# klokun.net
KiCad netlist of a schematic drawn in Altium Designer
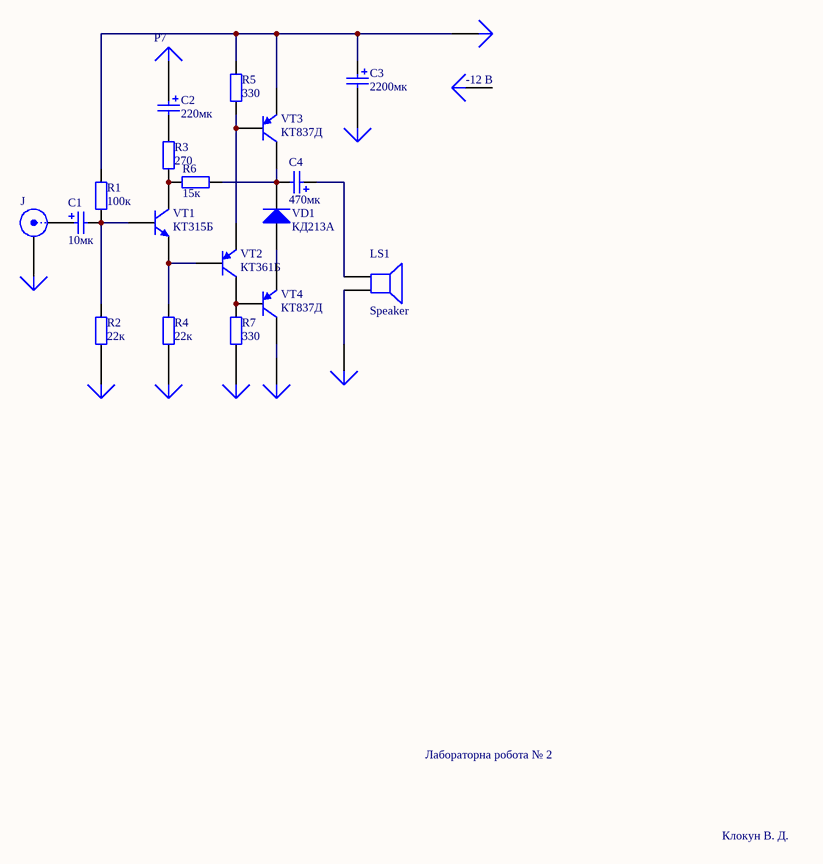
[diagram p0: klokun.SchDoc]

(export (version "E")
  (design (tool "Eeschema 10.0.6"))
  (components
    (comp (ref "C1")
      (value "10мк")
      (footprint "CAPPA14.05-10.5x6.3")
      (description "Polarized Capacitor (Axial)")
      (fields (field (name "Comment") "Cap Pol2") (field (name "PUBLISHER") "Altium Limited"))
      (libsource (lib "Miscellaneous Devices") (part "Cap Pol2"))
    )
    (comp (ref "C2")
      (value "220мк")
      (footprint "CAPPA14.05-10.5x6.3")
      (description "Polarized Capacitor (Axial)")
      (fields (field (name "Comment") "Cap Pol2") (field (name "PUBLISHER") "Altium Limited"))
      (libsource (lib "Miscellaneous Devices") (part "Cap Pol2"))
    )
    (comp (ref "C3")
      (value "2200мк")
      (footprint "CAPPA14.05-10.5x6.3")
      (description "Polarized Capacitor (Axial)")
      (fields (field (name "Comment") "Cap Pol2") (field (name "PUBLISHER") "Altium Limited"))
      (libsource (lib "Miscellaneous Devices") (part "Cap Pol2"))
    )
    (comp (ref "C4")
      (value "470мк")
      (footprint "CAPPA14.05-10.5x6.3")
      (description "Polarized Capacitor (Axial)")
      (fields (field (name "Comment") "Cap Pol2") (field (name "PUBLISHER") "Altium Limited"))
      (libsource (lib "Miscellaneous Devices") (part "Cap Pol2"))
    )
    (comp (ref "J")
      (value "BNC")
      (footprint "BNC_RA CON")
      (description "BNC Elbow Connector")
      (fields (field (name "PUBLISHER") "Altium Limited"))
      (libsource (lib "Miscellaneous Connectors") (part "BNC"))
    )
    (comp (ref "LS1")
      (value "Speaker")
      (footprint "PIN2")
      (description "Loudspeaker")
      (fields (field (name "PUBLISHER") "Altium Limited"))
      (libsource (lib "Miscellaneous Devices") (part "Speaker"))
    )
    (comp (ref "P1")
      (value "Plug")
      (footprint "PIN1")
      (fields (field (name "PUBLISHER") "Altium Limited"))
      (libsource (lib "Miscellaneous Connectors") (part "Plug"))
    )
    (comp (ref "P2")
      (value "Plug")
      (footprint "PIN1")
      (fields (field (name "PUBLISHER") "Altium Limited"))
      (libsource (lib "Miscellaneous Connectors") (part "Plug"))
    )
    (comp (ref "P3")
      (value "Plug")
      (footprint "PIN1")
      (fields (field (name "PUBLISHER") "Altium Limited"))
      (libsource (lib "Miscellaneous Connectors") (part "Plug"))
    )
    (comp (ref "P4")
      (value "Plug")
      (footprint "PIN1")
      (fields (field (name "PUBLISHER") "Altium Limited"))
      (libsource (lib "Miscellaneous Connectors") (part "Plug"))
    )
    (comp (ref "P5")
      (value "Plug")
      (footprint "PIN1")
      (fields (field (name "PUBLISHER") "Altium Limited"))
      (libsource (lib "Miscellaneous Connectors") (part "Plug"))
    )
    (comp (ref "P6")
      (value "Plug")
      (footprint "PIN1")
      (fields (field (name "PUBLISHER") "Altium Limited"))
      (libsource (lib "Miscellaneous Connectors") (part "Plug"))
    )
    (comp (ref "P7")
      (value "Plug")
      (footprint "PIN1")
      (fields (field (name "PUBLISHER") "Altium Limited"))
      (libsource (lib "Miscellaneous Connectors") (part "Plug"))
    )
    (comp (ref "P8")
      (value "Plug")
      (footprint "PIN1")
      (fields (field (name "PUBLISHER") "Altium Limited"))
      (libsource (lib "Miscellaneous Connectors") (part "Plug"))
    )
    (comp (ref "P9")
      (value "Plug")
      (footprint "PIN1")
      (fields (field (name "PUBLISHER") "Altium Limited"))
      (libsource (lib "Miscellaneous Connectors") (part "Plug"))
    )
    (comp (ref "P10")
      (value "-12 В")
      (footprint "PIN1")
      (description "Plug")
      (fields (field (name "PUBLISHER") "Altium Limited"))
      (libsource (lib "Miscellaneous Connectors") (part "Plug"))
    )
    (comp (ref "R1")
      (value "100к")
      (footprint "AXIAL-0.4")
      (description "Resistor")
      (fields (field (name "Comment") "Res2") (field (name "PUBLISHER") "Altium Limited"))
      (libsource (lib "Miscellaneous Devices") (part "Res2"))
    )
    (comp (ref "R2")
      (value "22к")
      (footprint "AXIAL-0.4")
      (description "Resistor")
      (fields (field (name "Comment") "Res2") (field (name "PUBLISHER") "Altium Limited"))
      (libsource (lib "Miscellaneous Devices") (part "Res2"))
    )
    (comp (ref "R3")
      (value "270")
      (footprint "AXIAL-0.4")
      (description "Resistor")
      (fields (field (name "Comment") "Res2") (field (name "PUBLISHER") "Altium Limited"))
      (libsource (lib "Miscellaneous Devices") (part "Res2"))
    )
    (comp (ref "R4")
      (value "22к")
      (footprint "AXIAL-0.4")
      (description "Resistor")
      (fields (field (name "Comment") "Res2") (field (name "PUBLISHER") "Altium Limited"))
      (libsource (lib "Miscellaneous Devices") (part "Res2"))
    )
    (comp (ref "R5")
      (value "330")
      (footprint "AXIAL-0.4")
      (description "Resistor")
      (fields (field (name "Comment") "Res2") (field (name "PUBLISHER") "Altium Limited"))
      (libsource (lib "Miscellaneous Devices") (part "Res2"))
    )
    (comp (ref "R6")
      (value "15к")
      (footprint "AXIAL-0.4")
      (description "Resistor")
      (fields (field (name "Comment") "Res2") (field (name "PUBLISHER") "Altium Limited"))
      (libsource (lib "") (part "Res2_1"))
    )
    (comp (ref "R7")
      (value "330")
      (footprint "AXIAL-0.4")
      (description "Resistor")
      (fields (field (name "Comment") "Res2") (field (name "PUBLISHER") "Altium Limited"))
      (libsource (lib "Miscellaneous Devices") (part "Res2"))
    )
    (comp (ref "VD1")
      (value "КД213А")
      (footprint "SMC")
      (description "Default Diode")
      (fields (field (name "PUBLISHER") "Altium Limited"))
      (libsource (lib "Miscellaneous Devices") (part "Diode"))
    )
    (comp (ref "VT1")
      (value "КТ315Б")
      (footprint "TO-226")
      (description "NPN Bipolar Transistor")
      (fields (field (name "PUBLISHER") "Altium Limited"))
      (libsource (lib "Miscellaneous Devices") (part "NPN"))
    )
    (comp (ref "VT2")
      (value "КТ361Б")
      (footprint "SOT-23B")
      (description "PNP Bipolar Transistor")
      (fields (field (name "PUBLISHER") "Altium Limited"))
      (libsource (lib "Miscellaneous Devices") (part "PNP"))
    )
    (comp (ref "VT3")
      (value "КТ837Д")
      (footprint "SOT-23B")
      (description "PNP Bipolar Transistor")
      (fields (field (name "PUBLISHER") "Altium Limited"))
      (libsource (lib "Miscellaneous Devices") (part "PNP"))
    )
    (comp (ref "VT4")
      (value "КТ837Д")
      (footprint "SOT-23B")
      (description "PNP Bipolar Transistor")
      (fields (field (name "PUBLISHER") "Altium Limited"))
      (libsource (lib "Miscellaneous Devices") (part "PNP"))
    )
  )
  (nets
    (net (code "1") (name "Net-(C2-Pad1)") (class "Default")
      (node (ref "C2") (pin "1") (pinfunction "1_1") (pintype "passive"))
      (node (ref "P7") (pin "1") (pinfunction "1_1") (pintype "passive"))
    )
    (net (code "2") (name "Net-(C2-Pad2)") (class "Default")
      (node (ref "C2") (pin "2") (pinfunction "2_2") (pintype "passive"))
      (node (ref "R3") (pin "2") (pinfunction "2_2") (pintype "passive"))
    )
    (net (code "3") (name "Net-(C3-Pad2)") (class "Default")
      (node (ref "C3") (pin "2") (pinfunction "2_2") (pintype "passive"))
      (node (ref "P1") (pin "1") (pinfunction "1_1") (pintype "passive"))
    )
    (net (code "4") (name "Net-(C4-Pad1)") (class "Default")
      (node (ref "C4") (pin "1") (pinfunction "1_1") (pintype "passive"))
      (node (ref "LS1") (pin "1") (pinfunction "1_1") (pintype "passive"))
    )
    (net (code "5") (name "Net-(J-X)") (class "Default")
      (node (ref "C1") (pin "1") (pinfunction "1_1") (pintype "passive"))
      (node (ref "J") (pin "1") (pinfunction "X_1") (pintype "passive"))
    )
    (net (code "6") (name "Net-(J-Y)") (class "Default")
      (node (ref "J") (pin "2") (pinfunction "Y_2") (pintype "passive"))
      (node (ref "P9") (pin "1") (pinfunction "1_1") (pintype "passive"))
    )
    (net (code "7") (name "Net-(LS1-Pad2)") (class "Default")
      (node (ref "LS1") (pin "2") (pinfunction "2_2") (pintype "passive"))
      (node (ref "P2") (pin "1") (pinfunction "1_1") (pintype "passive"))
    )
    (net (code "8") (name "Net-(P3-Pad1)") (class "Default")
      (node (ref "P3") (pin "1") (pinfunction "1_1") (pintype "passive"))
      (node (ref "R7") (pin "1") (pinfunction "1_1") (pintype "passive"))
    )
    (net (code "9") (name "Net-(P4-Pad1)") (class "Default")
      (node (ref "P4") (pin "1") (pinfunction "1_1") (pintype "passive"))
      (node (ref "R4") (pin "1") (pinfunction "1_1") (pintype "passive"))
    )
    (net (code "10") (name "Net-(P5-Pad1)") (class "Default")
      (node (ref "P5") (pin "1") (pinfunction "1_1") (pintype "passive"))
      (node (ref "R2") (pin "1") (pinfunction "1_1") (pintype "passive"))
    )
    (net (code "11") (name "Net-(VD1-A)") (class "Default")
      (node (ref "VD1") (pin "1") (pinfunction "A_1") (pintype "passive"))
      (node (ref "VT4") (pin "3") (pinfunction "E_3") (pintype "passive"))
    )
    (net (code "12") (name "Net-(VD1-K)") (class "Default")
      (node (ref "C4") (pin "2") (pinfunction "2_2") (pintype "passive"))
      (node (ref "R6") (pin "2") (pinfunction "2_2") (pintype "passive"))
      (node (ref "VD1") (pin "2") (pinfunction "K_2") (pintype "passive"))
      (node (ref "VT3") (pin "1") (pinfunction "C_1") (pintype "passive"))
    )
    (net (code "13") (name "Net-(VT1-B)") (class "Default")
      (node (ref "C1") (pin "2") (pinfunction "2_2") (pintype "passive"))
      (node (ref "R1") (pin "1") (pinfunction "1_1") (pintype "passive"))
      (node (ref "R2") (pin "2") (pinfunction "2_2") (pintype "passive"))
      (node (ref "VT1") (pin "2") (pinfunction "B_2") (pintype "passive"))
    )
    (net (code "14") (name "Net-(VT1-C)") (class "Default")
      (node (ref "R3") (pin "1") (pinfunction "1_1") (pintype "passive"))
      (node (ref "R6") (pin "1") (pinfunction "1_1") (pintype "passive"))
      (node (ref "VT1") (pin "1") (pinfunction "C_1") (pintype "passive"))
    )
    (net (code "15") (name "Net-(VT1-E)") (class "Default")
      (node (ref "R4") (pin "2") (pinfunction "2_2") (pintype "passive"))
      (node (ref "VT1") (pin "3") (pinfunction "E_3") (pintype "passive"))
      (node (ref "VT2") (pin "2") (pinfunction "B_2") (pintype "passive"))
    )
    (net (code "16") (name "Net-(VT2-C)") (class "Default")
      (node (ref "R7") (pin "2") (pinfunction "2_2") (pintype "passive"))
      (node (ref "VT2") (pin "1") (pinfunction "C_1") (pintype "passive"))
      (node (ref "VT4") (pin "2") (pinfunction "B_2") (pintype "passive"))
    )
    (net (code "17") (name "Net-(VT2-E)") (class "Default")
      (node (ref "R5") (pin "1") (pinfunction "1_1") (pintype "passive"))
      (node (ref "VT2") (pin "3") (pinfunction "E_3") (pintype "passive"))
      (node (ref "VT3") (pin "2") (pinfunction "B_2") (pintype "passive"))
    )
    (net (code "18") (name "Net-(VT3-E)") (class "Default")
      (node (ref "C3") (pin "1") (pinfunction "1_1") (pintype "passive"))
      (node (ref "P6") (pin "1") (pinfunction "1_1") (pintype "passive"))
      (node (ref "R1") (pin "2") (pinfunction "2_2") (pintype "passive"))
      (node (ref "R5") (pin "2") (pinfunction "2_2") (pintype "passive"))
      (node (ref "VT3") (pin "3") (pinfunction "E_3") (pintype "passive"))
    )
    (net (code "19") (name "Net-(VT4-C)") (class "Default")
      (node (ref "P8") (pin "1") (pinfunction "1_1") (pintype "passive"))
      (node (ref "VT4") (pin "1") (pinfunction "C_1") (pintype "passive"))
    )
    (net (code "20") (name "unconnected-(P10-Pad1)") (class "Default")
      (node (ref "P10") (pin "1") (pinfunction "1_1") (pintype "passive"))
    )
  )
)
